# 1-Schematic_LLU_PCB.net
KiCad netlist of a schematic drawn in EasyEDA
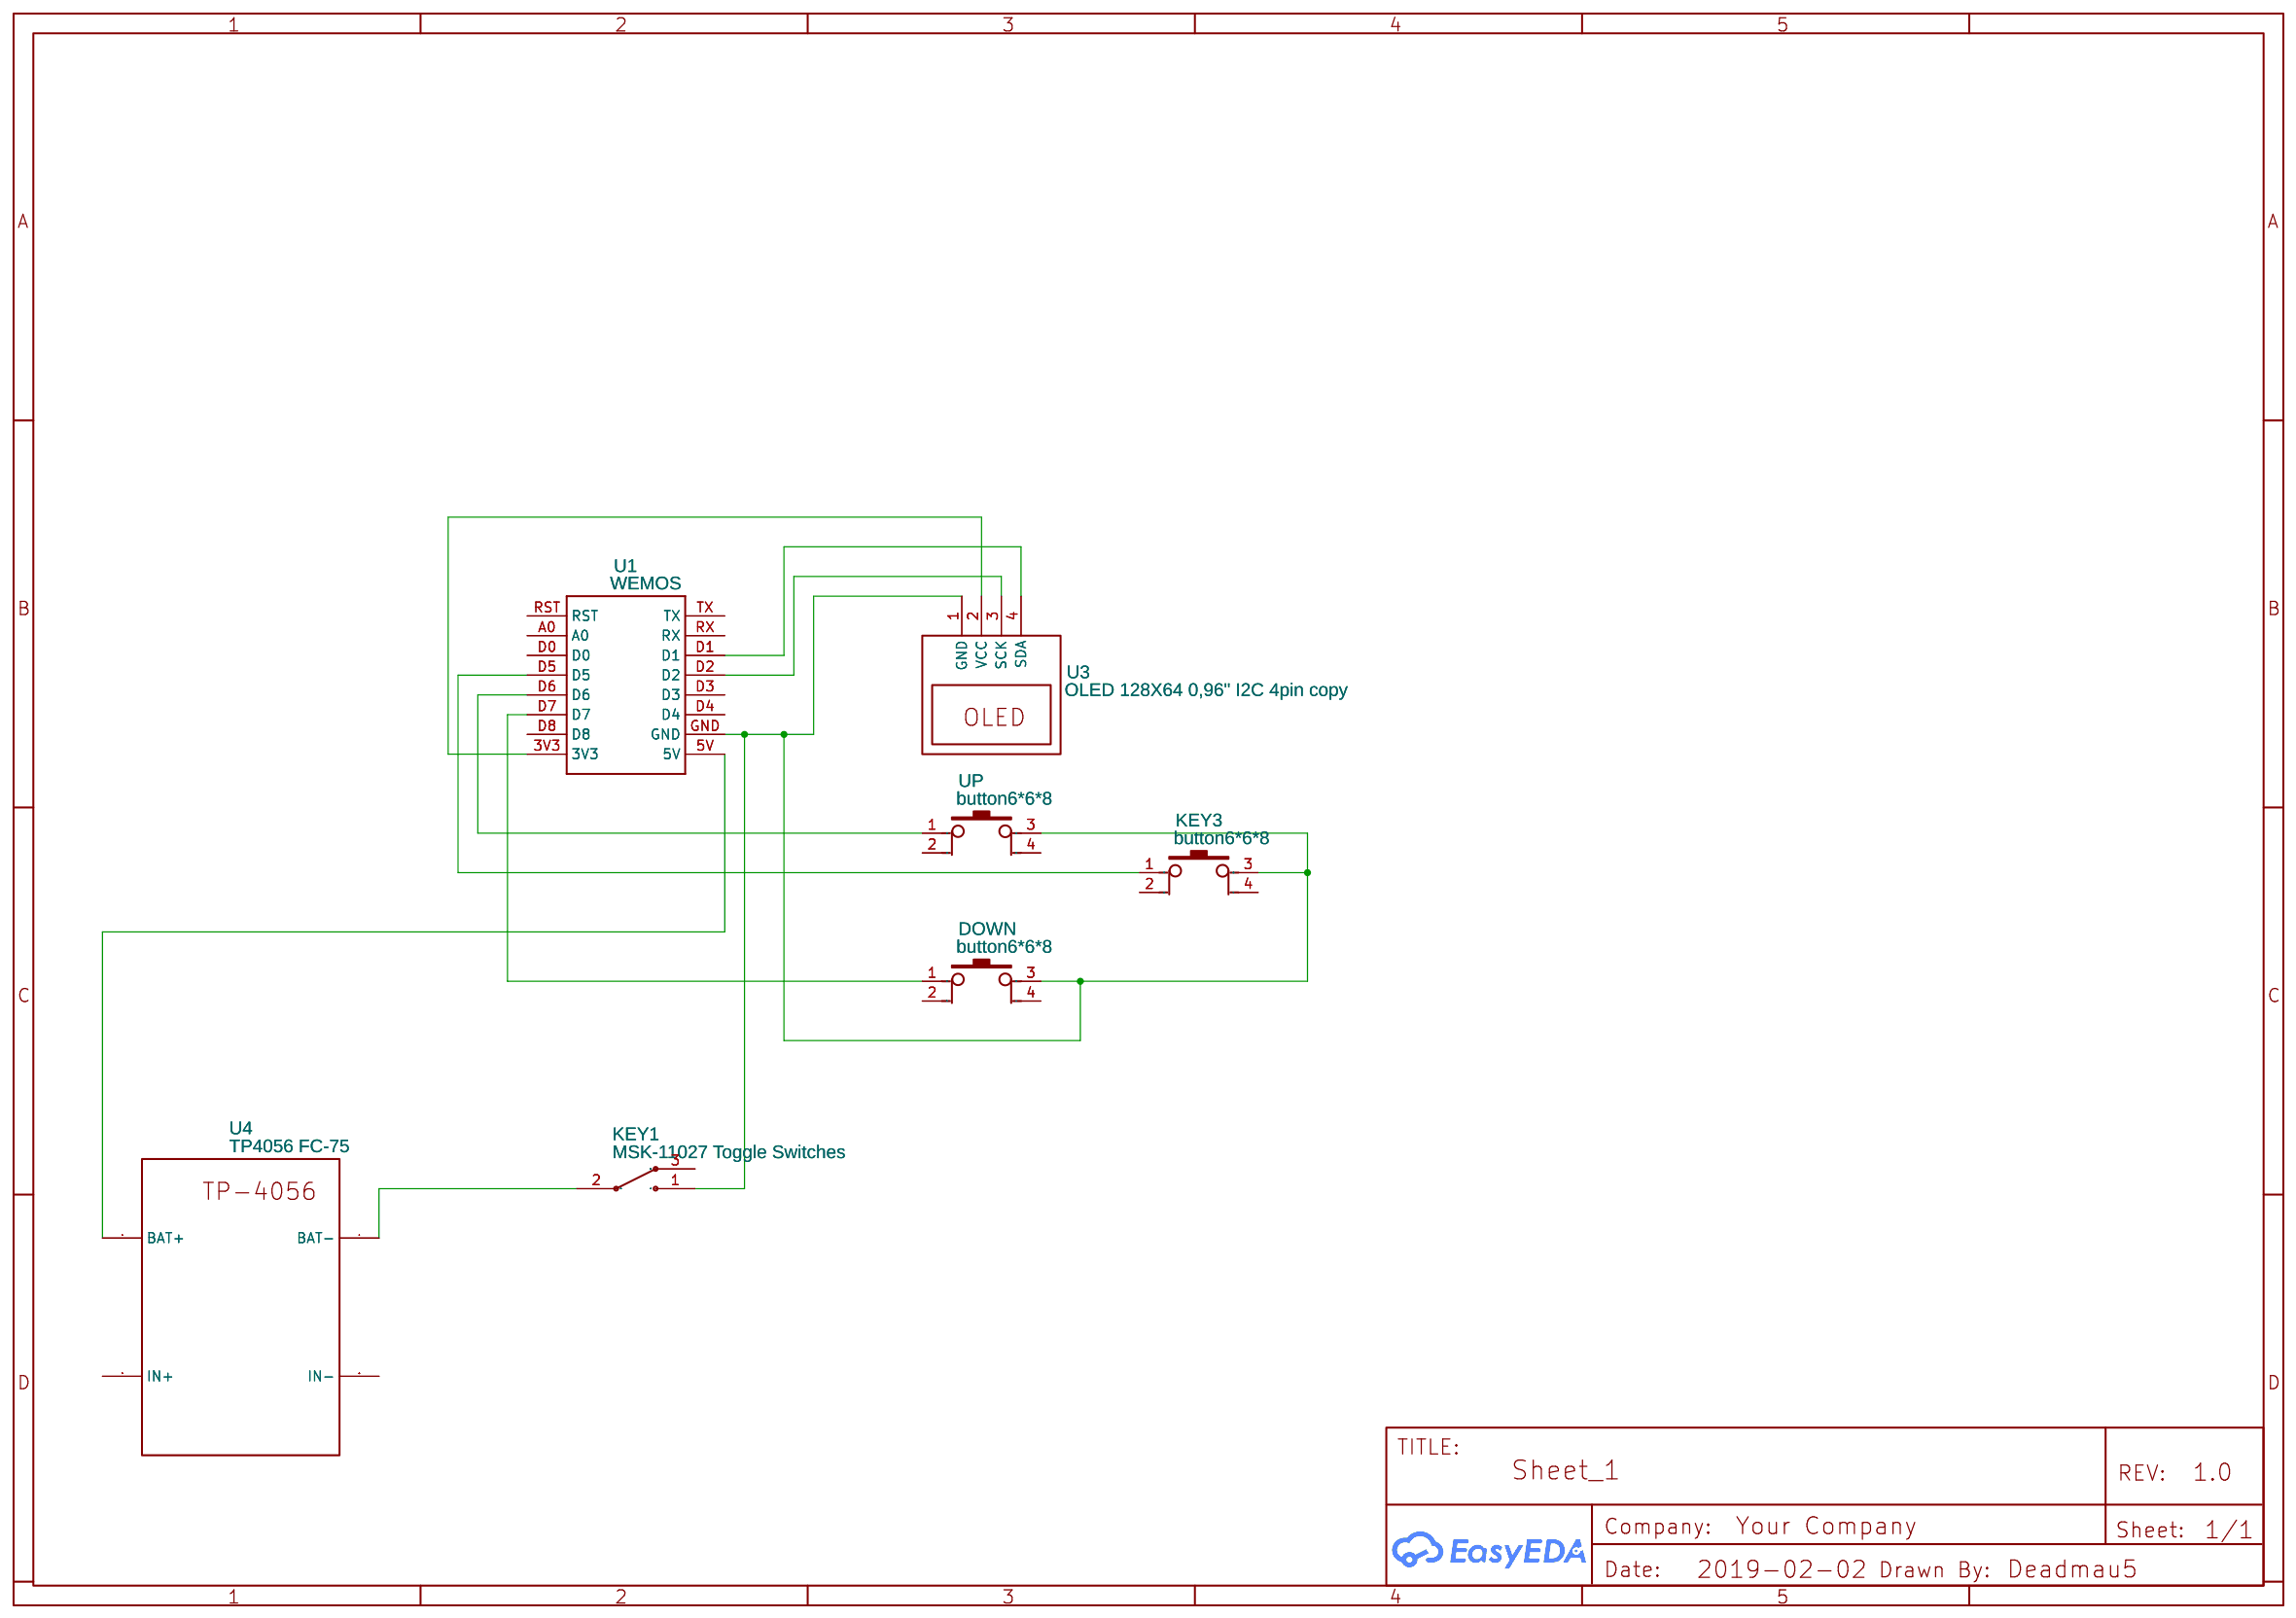
[diagram p0: schematic sheet]

(export (version "E")
  (design (tool "Eeschema 10.0.6"))
  (components
    (comp (ref "DOWN")
      (value "button6*6*8")
      (fields (field (name "BOM_Supplier Part") "C59982"))
      (libsource (lib "") (part "Unknown_490_490"))
    )
    (comp (ref "KEY1")
      (value "MSK-11027 Toggle Switches")
      (fields (field (name "BOM_Supplier Part") "C21381"))
      (libsource (lib "") (part "Unknown_315_585"))
    )
    (comp (ref "KEY3")
      (value "button6*6*8")
      (fields (field (name "BOM_Supplier Part") "C59982"))
      (libsource (lib "") (part "Unknown_600_435"))
    )
    (comp (ref "U1")
      (value "WEMOS")
      (fields (field (name "BOM_Manufacturer Part") "?"))
      (libsource (lib "") (part "Unknown_280_385"))
    )
    (comp (ref "U3")
      (value "OLED 128X64 0,96\" I2C 4pin copy")
      (fields (field (name "BOM_Manufacturer Part") "SSD1306 I2C OLED"))
      (libsource (lib "") (part "Unknown_460_295"))
    )
    (comp (ref "U4") (value "TP4056 FC-75") (libsource (lib "") (part "Unknown_115_660")))
    (comp (ref "UP")
      (value "button6*6*8")
      (fields (field (name "BOM_Supplier Part") "C59982"))
      (libsource (lib "") (part "Unknown_490_415"))
    )
  )
  (nets
    (net (code "1") (name "Net-(DOWN-Pad1)") (class "Default")
      (node (ref "DOWN") (pin "1") (pinfunction "1_1") (pintype "input"))
      (node (ref "U1") (pin "D7") (pinfunction "D7_D7") (pintype "unspecified"))
    )
    (net (code "2") (name "Net-(KEY3-Pad1)") (class "Default")
      (node (ref "KEY3") (pin "1") (pinfunction "1_1") (pintype "input"))
      (node (ref "U1") (pin "D5") (pinfunction "D5_D5") (pintype "unspecified"))
    )
    (net (code "3") (name "Net-(U1-PadD6)") (class "Default")
      (node (ref "U1") (pin "D6") (pinfunction "D6_D6") (pintype "unspecified"))
      (node (ref "UP") (pin "1") (pinfunction "1_1") (pintype "input"))
    )
    (net (code "4") (name "Net-(U3-GND)") (class "Default")
      (node (ref "DOWN") (pin "3") (pinfunction "3_3") (pintype "input"))
      (node (ref "KEY1") (pin "1") (pinfunction "1_1") (pintype "unspecified"))
      (node (ref "KEY3") (pin "3") (pinfunction "3_3") (pintype "input"))
      (node (ref "U1") (pin "GND") (pinfunction "GND_GND") (pintype "unspecified"))
      (node (ref "U3") (pin "1") (pinfunction "GND_1") (pintype "unspecified"))
      (node (ref "UP") (pin "3") (pinfunction "3_3") (pintype "input"))
    )
    (net (code "5") (name "Net-(U3-SCK)") (class "Default")
      (node (ref "U1") (pin "D2") (pinfunction "D2_D2") (pintype "unspecified"))
      (node (ref "U3") (pin "3") (pinfunction "SCK_3") (pintype "unspecified"))
    )
    (net (code "6") (name "Net-(U3-SDA)") (class "Default")
      (node (ref "U1") (pin "D1") (pinfunction "D1_D1") (pintype "unspecified"))
      (node (ref "U3") (pin "4") (pinfunction "SDA_4") (pintype "unspecified"))
    )
    (net (code "7") (name "Net-(U3-VCC)") (class "Default")
      (node (ref "U1") (pin "3V3") (pinfunction "3V3_3V3") (pintype "unspecified"))
      (node (ref "U3") (pin "2") (pinfunction "VCC_2") (pintype "unspecified"))
    )
    (net (code "8") (name "Net-(U4-BAT+)") (class "Default")
      (node (ref "U1") (pin "5V") (pinfunction "5V_5V") (pintype "unspecified"))
      (node (ref "U4") (pin "1") (pinfunction "BAT+_1") (pintype "unspecified"))
    )
    (net (code "9") (name "Net-(U4-BAT-)") (class "Default")
      (node (ref "KEY1") (pin "2") (pinfunction "2_2") (pintype "unspecified"))
      (node (ref "U4") (pin "4") (pinfunction "BAT-_4") (pintype "unspecified"))
    )
    (net (code "10") (name "unconnected-(DOWN-Pad2)") (class "Default")
      (node (ref "DOWN") (pin "2") (pinfunction "2_2") (pintype "input"))
    )
    (net (code "11") (name "unconnected-(DOWN-Pad4)") (class "Default")
      (node (ref "DOWN") (pin "4") (pinfunction "4_4") (pintype "input"))
    )
    (net (code "12") (name "unconnected-(KEY1-Pad3)") (class "Default")
      (node (ref "KEY1") (pin "3") (pinfunction "3_3") (pintype "unspecified"))
    )
    (net (code "13") (name "unconnected-(KEY3-Pad2)") (class "Default")
      (node (ref "KEY3") (pin "2") (pinfunction "2_2") (pintype "input"))
    )
    (net (code "14") (name "unconnected-(KEY3-Pad4)") (class "Default")
      (node (ref "KEY3") (pin "4") (pinfunction "4_4") (pintype "input"))
    )
    (net (code "15") (name "unconnected-(U1-PadA0)") (class "Default")
      (node (ref "U1") (pin "A0") (pinfunction "A0_A0") (pintype "unspecified"))
    )
    (net (code "16") (name "unconnected-(U1-PadD0)") (class "Default")
      (node (ref "U1") (pin "D0") (pinfunction "D0_D0") (pintype "unspecified"))
    )
    (net (code "17") (name "unconnected-(U1-PadD3)") (class "Default")
      (node (ref "U1") (pin "D3") (pinfunction "D3_D3") (pintype "unspecified"))
    )
    (net (code "18") (name "unconnected-(U1-PadD4)") (class "Default")
      (node (ref "U1") (pin "D4") (pinfunction "D4_D4") (pintype "unspecified"))
    )
    (net (code "19") (name "unconnected-(U1-PadD8)") (class "Default")
      (node (ref "U1") (pin "D8") (pinfunction "D8_D8") (pintype "unspecified"))
    )
    (net (code "20") (name "unconnected-(U1-PadRST)") (class "Default")
      (node (ref "U1") (pin "RST") (pinfunction "RST_RST") (pintype "unspecified"))
    )
    (net (code "21") (name "unconnected-(U1-PadRX)") (class "Default")
      (node (ref "U1") (pin "RX") (pinfunction "RX_RX") (pintype "unspecified"))
    )
    (net (code "22") (name "unconnected-(U1-PadTX)") (class "Default")
      (node (ref "U1") (pin "TX") (pinfunction "TX_TX") (pintype "unspecified"))
    )
    (net (code "23") (name "unconnected-(U4-IN+-Pad2)") (class "Default")
      (node (ref "U4") (pin "2") (pinfunction "IN+_2") (pintype "unspecified"))
    )
    (net (code "24") (name "unconnected-(U4-IN--Pad3)") (class "Default")
      (node (ref "U4") (pin "3") (pinfunction "IN-_3") (pintype "unspecified"))
    )
    (net (code "25") (name "unconnected-(UP-Pad2)") (class "Default")
      (node (ref "UP") (pin "2") (pinfunction "2_2") (pintype "input"))
    )
    (net (code "26") (name "unconnected-(UP-Pad4)") (class "Default")
      (node (ref "UP") (pin "4") (pinfunction "4_4") (pintype "input"))
    )
  )
)
